# V3.net
KiCad netlist of a schematic drawn in Altium Designer
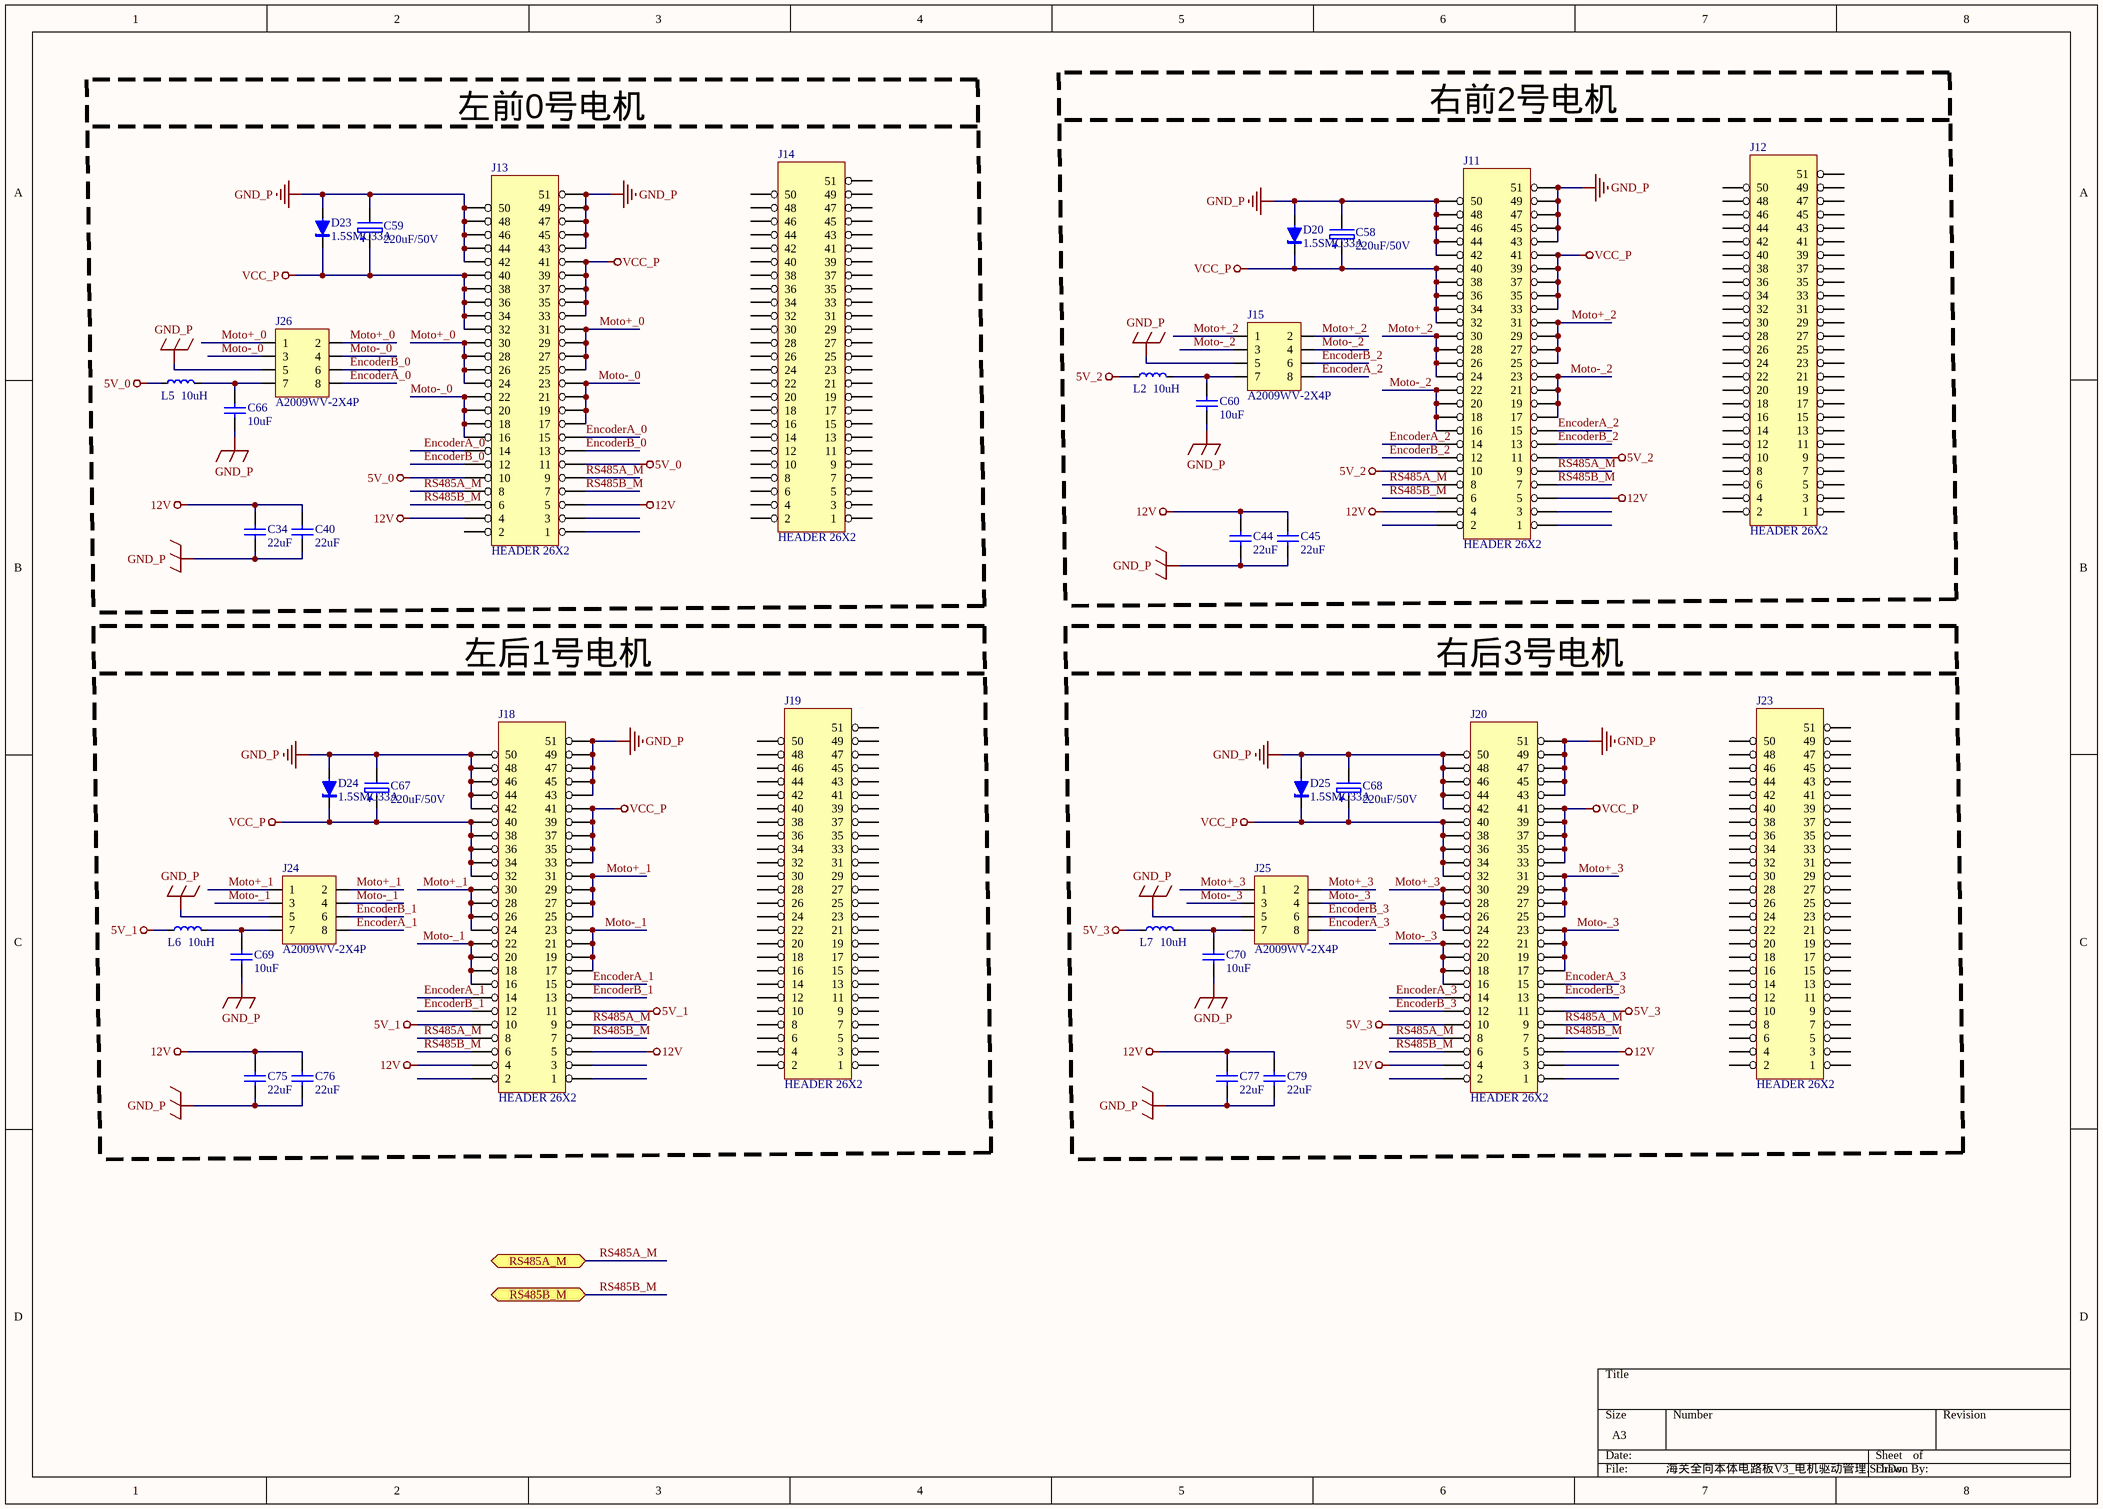
[diagram p0: 海关全向本体电路板V3_电机驱动管理.SchDoc]

(export (version "E")
  (design (tool "Eeschema 10.0.6"))
  (components
    (comp (ref "C34")
      (value "22uF")
      (footprint "C1206-S")
      (description "CAP")
      (fields (field (name "PUBLISHER") "Altium Limited"))
      (libsource (lib "Passive Components Class") (part "CAP"))
    )
    (comp (ref "C40")
      (value "22uF")
      (footprint "C1206-S")
      (description "CAP")
      (fields (field (name "PUBLISHER") "Altium Limited"))
      (libsource (lib "Passive Components Class") (part "CAP"))
    )
    (comp (ref "C44")
      (value "22uF")
      (footprint "C1206-S")
      (description "CAP")
      (fields (field (name "PUBLISHER") "Altium Limited"))
      (libsource (lib "Passive Components Class") (part "CAP"))
    )
    (comp (ref "C45")
      (value "22uF")
      (footprint "C1206-S")
      (description "CAP")
      (fields (field (name "PUBLISHER") "Altium Limited"))
      (libsource (lib "Passive Components Class") (part "CAP"))
    )
    (comp (ref "C58")
      (value "220uF/50V")
      (footprint "CAPPR-10X10-SM")
      (description "Electrolytic Capacitor")
      (libsource (lib "*") (part "ELECTRO"))
    )
    (comp (ref "C59")
      (value "220uF/50V")
      (footprint "CAPPR-10X10-SM")
      (description "Electrolytic Capacitor")
      (libsource (lib "*") (part "ELECTRO"))
    )
    (comp (ref "C60")
      (value "10uF")
      (footprint "C0603-S")
      (description "CAP")
      (fields (field (name "PUBLISHER") "Altium Limited"))
      (libsource (lib "Passive Components Class") (part "CAP"))
    )
    (comp (ref "C66")
      (value "10uF")
      (footprint "C0603-S")
      (description "CAP")
      (fields (field (name "PUBLISHER") "Altium Limited"))
      (libsource (lib "Passive Components Class") (part "CAP"))
    )
    (comp (ref "C67")
      (value "220uF/50V")
      (footprint "CAPPR-10X10-SM")
      (description "Electrolytic Capacitor")
      (libsource (lib "*") (part "ELECTRO"))
    )
    (comp (ref "C68")
      (value "220uF/50V")
      (footprint "CAPPR-10X10-SM")
      (description "Electrolytic Capacitor")
      (libsource (lib "*") (part "ELECTRO"))
    )
    (comp (ref "C69")
      (value "10uF")
      (footprint "C0603-S")
      (description "CAP")
      (fields (field (name "PUBLISHER") "Altium Limited"))
      (libsource (lib "Passive Components Class") (part "CAP"))
    )
    (comp (ref "C70")
      (value "10uF")
      (footprint "C0603-S")
      (description "CAP")
      (fields (field (name "PUBLISHER") "Altium Limited"))
      (libsource (lib "Passive Components Class") (part "CAP"))
    )
    (comp (ref "C75")
      (value "22uF")
      (footprint "C1206-S")
      (description "CAP")
      (fields (field (name "PUBLISHER") "Altium Limited"))
      (libsource (lib "Passive Components Class") (part "CAP"))
    )
    (comp (ref "C76")
      (value "22uF")
      (footprint "C1206-S")
      (description "CAP")
      (fields (field (name "PUBLISHER") "Altium Limited"))
      (libsource (lib "Passive Components Class") (part "CAP"))
    )
    (comp (ref "C77")
      (value "22uF")
      (footprint "C1206-S")
      (description "CAP")
      (fields (field (name "PUBLISHER") "Altium Limited"))
      (libsource (lib "Passive Components Class") (part "CAP"))
    )
    (comp (ref "C79")
      (value "22uF")
      (footprint "C1206-S")
      (description "CAP")
      (fields (field (name "PUBLISHER") "Altium Limited"))
      (libsource (lib "Passive Components Class") (part "CAP"))
    )
    (comp (ref "D20")
      (value "1.5SMC33A")
      (footprint "SMC-S")
      (description "Small Signal Zener Diodes")
      (libsource (lib "Passive Components Class") (part "DIODE-ZENER"))
    )
    (comp (ref "D23")
      (value "1.5SMC33A")
      (footprint "SMC-S")
      (description "Small Signal Zener Diodes")
      (libsource (lib "Passive Components Class") (part "DIODE-ZENER"))
    )
    (comp (ref "D24")
      (value "1.5SMC33A")
      (footprint "SMC-S")
      (description "Small Signal Zener Diodes")
      (libsource (lib "Passive Components Class") (part "DIODE-ZENER"))
    )
    (comp (ref "D25")
      (value "1.5SMC33A")
      (footprint "SMC-S")
      (description "Small Signal Zener Diodes")
      (libsource (lib "Passive Components Class") (part "DIODE-ZENER"))
    )
    (comp (ref "J11")
      (value "HEADER 26X2")
      (footprint "DF9-51P-1V")
      (libsource (lib "Connector Class") (part "HEADER 35X2_1"))
    )
    (comp (ref "J12")
      (value "HEADER 26X2")
      (footprint "DF9-51P-1V")
      (libsource (lib "Connector Class") (part "HEADER 35X2_1"))
    )
    (comp (ref "J13")
      (value "HEADER 26X2")
      (footprint "DF9-51P-1V")
      (libsource (lib "Connector Class") (part "HEADER 35X2_1"))
    )
    (comp (ref "J14")
      (value "HEADER 26X2")
      (footprint "DF9-51P-1V")
      (libsource (lib "Connector Class") (part "HEADER 35X2_1"))
    )
    (comp (ref "J15")
      (value "A2009WV-2X4P")
      (footprint "A2009WV-2X4P")
      (libsource (lib "Connector Class") (part "A2009WV-2X5P"))
    )
    (comp (ref "J18")
      (value "HEADER 26X2")
      (footprint "DF9-51P-1V")
      (libsource (lib "Connector Class") (part "HEADER 35X2_1"))
    )
    (comp (ref "J19")
      (value "HEADER 26X2")
      (footprint "DF9-51P-1V")
      (libsource (lib "Connector Class") (part "HEADER 35X2_1"))
    )
    (comp (ref "J20")
      (value "HEADER 26X2")
      (footprint "DF9-51P-1V")
      (libsource (lib "Connector Class") (part "HEADER 35X2_1"))
    )
    (comp (ref "J23")
      (value "HEADER 26X2")
      (footprint "DF9-51P-1V")
      (libsource (lib "Connector Class") (part "HEADER 35X2_1"))
    )
    (comp (ref "J24")
      (value "A2009WV-2X4P")
      (footprint "A2009WV-2X4P")
      (libsource (lib "Connector Class") (part "A2009WV-2X5P"))
    )
    (comp (ref "J25")
      (value "A2009WV-2X4P")
      (footprint "A2009WV-2X4P")
      (libsource (lib "Connector Class") (part "A2009WV-2X5P"))
    )
    (comp (ref "J26")
      (value "A2009WV-2X4P")
      (footprint "A2009WV-2X4P")
      (libsource (lib "Connector Class") (part "HEADER2X4"))
    )
    (comp (ref "L2")
      (value "10uH")
      (footprint "L0805-C")
      (description "INDUCTOR")
      (fields (field (name "PUBLISHER") "Altium Limited"))
      (libsource (lib "Passive Components Class") (part "INDUCTOR"))
    )
    (comp (ref "L5")
      (value "10uH")
      (footprint "L0805-C")
      (description "INDUCTOR")
      (fields (field (name "PUBLISHER") "Altium Limited"))
      (libsource (lib "Passive Components Class") (part "INDUCTOR"))
    )
    (comp (ref "L6")
      (value "10uH")
      (footprint "L0805-C")
      (description "INDUCTOR")
      (fields (field (name "PUBLISHER") "Altium Limited"))
      (libsource (lib "Passive Components Class") (part "INDUCTOR"))
    )
    (comp (ref "L7")
      (value "10uH")
      (footprint "L0805-C")
      (description "INDUCTOR")
      (fields (field (name "PUBLISHER") "Altium Limited"))
      (libsource (lib "Passive Components Class") (part "INDUCTOR"))
    )
  )
  (nets
    (net (code "1") (name "/EncoderA_0") (class "Default")
      (node (ref "J13") (pin "14") (pinfunction "14_14") (pintype "passive"))
      (node (ref "J13") (pin "15") (pinfunction "15_15") (pintype "passive"))
      (node (ref "J26") (pin "8") (pinfunction "8_8") (pintype "passive"))
    )
    (net (code "2") (name "/EncoderA_1") (class "Default")
      (node (ref "J18") (pin "14") (pinfunction "14_14") (pintype "passive"))
      (node (ref "J18") (pin "15") (pinfunction "15_15") (pintype "passive"))
      (node (ref "J24") (pin "8") (pinfunction "8_8") (pintype "passive"))
    )
    (net (code "3") (name "/EncoderA_2") (class "Default")
      (node (ref "J11") (pin "14") (pinfunction "14_14") (pintype "passive"))
      (node (ref "J11") (pin "15") (pinfunction "15_15") (pintype "passive"))
      (node (ref "J15") (pin "8") (pinfunction "8_8") (pintype "passive"))
    )
    (net (code "4") (name "/EncoderA_3") (class "Default")
      (node (ref "J20") (pin "14") (pinfunction "14_14") (pintype "passive"))
      (node (ref "J20") (pin "15") (pinfunction "15_15") (pintype "passive"))
      (node (ref "J25") (pin "8") (pinfunction "8_8") (pintype "passive"))
    )
    (net (code "5") (name "/EncoderB_0") (class "Default")
      (node (ref "J13") (pin "12") (pinfunction "12_12") (pintype "passive"))
      (node (ref "J13") (pin "13") (pinfunction "13_13") (pintype "passive"))
      (node (ref "J26") (pin "6") (pinfunction "6_6") (pintype "passive"))
    )
    (net (code "6") (name "/EncoderB_1") (class "Default")
      (node (ref "J18") (pin "12") (pinfunction "12_12") (pintype "passive"))
      (node (ref "J18") (pin "13") (pinfunction "13_13") (pintype "passive"))
      (node (ref "J24") (pin "6") (pinfunction "6_6") (pintype "passive"))
    )
    (net (code "7") (name "/EncoderB_2") (class "Default")
      (node (ref "J11") (pin "12") (pinfunction "12_12") (pintype "passive"))
      (node (ref "J11") (pin "13") (pinfunction "13_13") (pintype "passive"))
      (node (ref "J15") (pin "6") (pinfunction "6_6") (pintype "passive"))
    )
    (net (code "8") (name "/EncoderB_3") (class "Default")
      (node (ref "J20") (pin "12") (pinfunction "12_12") (pintype "passive"))
      (node (ref "J20") (pin "13") (pinfunction "13_13") (pintype "passive"))
      (node (ref "J25") (pin "6") (pinfunction "6_6") (pintype "passive"))
    )
    (net (code "9") (name "/Moto+_0") (class "Default")
      (node (ref "J13") (pin "24") (pinfunction "24_24") (pintype "passive"))
      (node (ref "J13") (pin "25") (pinfunction "25_25") (pintype "passive"))
      (node (ref "J13") (pin "26") (pinfunction "26_26") (pintype "passive"))
      (node (ref "J13") (pin "27") (pinfunction "27_27") (pintype "passive"))
      (node (ref "J13") (pin "28") (pinfunction "28_28") (pintype "passive"))
      (node (ref "J13") (pin "29") (pinfunction "29_29") (pintype "passive"))
      (node (ref "J13") (pin "30") (pinfunction "30_30") (pintype "passive"))
      (node (ref "J13") (pin "31") (pinfunction "31_31") (pintype "passive"))
      (node (ref "J26") (pin "1") (pinfunction "1_1") (pintype "passive"))
      (node (ref "J26") (pin "2") (pinfunction "2_2") (pintype "passive"))
    )
    (net (code "10") (name "/Moto+_1") (class "Default")
      (node (ref "J18") (pin "24") (pinfunction "24_24") (pintype "passive"))
      (node (ref "J18") (pin "25") (pinfunction "25_25") (pintype "passive"))
      (node (ref "J18") (pin "26") (pinfunction "26_26") (pintype "passive"))
      (node (ref "J18") (pin "27") (pinfunction "27_27") (pintype "passive"))
      (node (ref "J18") (pin "28") (pinfunction "28_28") (pintype "passive"))
      (node (ref "J18") (pin "29") (pinfunction "29_29") (pintype "passive"))
      (node (ref "J18") (pin "30") (pinfunction "30_30") (pintype "passive"))
      (node (ref "J18") (pin "31") (pinfunction "31_31") (pintype "passive"))
      (node (ref "J24") (pin "1") (pinfunction "1_1") (pintype "passive"))
      (node (ref "J24") (pin "2") (pinfunction "2_2") (pintype "passive"))
    )
    (net (code "11") (name "/Moto+_2") (class "Default")
      (node (ref "J11") (pin "24") (pinfunction "24_24") (pintype "passive"))
      (node (ref "J11") (pin "25") (pinfunction "25_25") (pintype "passive"))
      (node (ref "J11") (pin "26") (pinfunction "26_26") (pintype "passive"))
      (node (ref "J11") (pin "27") (pinfunction "27_27") (pintype "passive"))
      (node (ref "J11") (pin "28") (pinfunction "28_28") (pintype "passive"))
      (node (ref "J11") (pin "29") (pinfunction "29_29") (pintype "passive"))
      (node (ref "J11") (pin "30") (pinfunction "30_30") (pintype "passive"))
      (node (ref "J11") (pin "31") (pinfunction "31_31") (pintype "passive"))
      (node (ref "J15") (pin "1") (pinfunction "1_1") (pintype "passive"))
      (node (ref "J15") (pin "2") (pinfunction "2_2") (pintype "passive"))
    )
    (net (code "12") (name "/Moto+_3") (class "Default")
      (node (ref "J20") (pin "24") (pinfunction "24_24") (pintype "passive"))
      (node (ref "J20") (pin "25") (pinfunction "25_25") (pintype "passive"))
      (node (ref "J20") (pin "26") (pinfunction "26_26") (pintype "passive"))
      (node (ref "J20") (pin "27") (pinfunction "27_27") (pintype "passive"))
      (node (ref "J20") (pin "28") (pinfunction "28_28") (pintype "passive"))
      (node (ref "J20") (pin "29") (pinfunction "29_29") (pintype "passive"))
      (node (ref "J20") (pin "30") (pinfunction "30_30") (pintype "passive"))
      (node (ref "J20") (pin "31") (pinfunction "31_31") (pintype "passive"))
      (node (ref "J25") (pin "1") (pinfunction "1_1") (pintype "passive"))
      (node (ref "J25") (pin "2") (pinfunction "2_2") (pintype "passive"))
    )
    (net (code "13") (name "/Moto-_0") (class "Default")
      (node (ref "J13") (pin "16") (pinfunction "16_16") (pintype "passive"))
      (node (ref "J13") (pin "17") (pinfunction "17_17") (pintype "passive"))
      (node (ref "J13") (pin "18") (pinfunction "18_18") (pintype "passive"))
      (node (ref "J13") (pin "19") (pinfunction "19_19") (pintype "passive"))
      (node (ref "J13") (pin "20") (pinfunction "20_20") (pintype "passive"))
      (node (ref "J13") (pin "21") (pinfunction "21_21") (pintype "passive"))
      (node (ref "J13") (pin "22") (pinfunction "22_22") (pintype "passive"))
      (node (ref "J13") (pin "23") (pinfunction "23_23") (pintype "passive"))
      (node (ref "J26") (pin "3") (pinfunction "3_3") (pintype "passive"))
      (node (ref "J26") (pin "4") (pinfunction "4_4") (pintype "passive"))
    )
    (net (code "14") (name "/Moto-_1") (class "Default")
      (node (ref "J18") (pin "16") (pinfunction "16_16") (pintype "passive"))
      (node (ref "J18") (pin "17") (pinfunction "17_17") (pintype "passive"))
      (node (ref "J18") (pin "18") (pinfunction "18_18") (pintype "passive"))
      (node (ref "J18") (pin "19") (pinfunction "19_19") (pintype "passive"))
      (node (ref "J18") (pin "20") (pinfunction "20_20") (pintype "passive"))
      (node (ref "J18") (pin "21") (pinfunction "21_21") (pintype "passive"))
      (node (ref "J18") (pin "22") (pinfunction "22_22") (pintype "passive"))
      (node (ref "J18") (pin "23") (pinfunction "23_23") (pintype "passive"))
      (node (ref "J24") (pin "3") (pinfunction "3_3") (pintype "passive"))
      (node (ref "J24") (pin "4") (pinfunction "4_4") (pintype "passive"))
    )
    (net (code "15") (name "/Moto-_2") (class "Default")
      (node (ref "J11") (pin "16") (pinfunction "16_16") (pintype "passive"))
      (node (ref "J11") (pin "17") (pinfunction "17_17") (pintype "passive"))
      (node (ref "J11") (pin "18") (pinfunction "18_18") (pintype "passive"))
      (node (ref "J11") (pin "19") (pinfunction "19_19") (pintype "passive"))
      (node (ref "J11") (pin "20") (pinfunction "20_20") (pintype "passive"))
      (node (ref "J11") (pin "21") (pinfunction "21_21") (pintype "passive"))
      (node (ref "J11") (pin "22") (pinfunction "22_22") (pintype "passive"))
      (node (ref "J11") (pin "23") (pinfunction "23_23") (pintype "passive"))
      (node (ref "J15") (pin "3") (pinfunction "3_3") (pintype "passive"))
      (node (ref "J15") (pin "4") (pinfunction "4_4") (pintype "passive"))
    )
    (net (code "16") (name "/Moto-_3") (class "Default")
      (node (ref "J20") (pin "16") (pinfunction "16_16") (pintype "passive"))
      (node (ref "J20") (pin "17") (pinfunction "17_17") (pintype "passive"))
      (node (ref "J20") (pin "18") (pinfunction "18_18") (pintype "passive"))
      (node (ref "J20") (pin "19") (pinfunction "19_19") (pintype "passive"))
      (node (ref "J20") (pin "20") (pinfunction "20_20") (pintype "passive"))
      (node (ref "J20") (pin "21") (pinfunction "21_21") (pintype "passive"))
      (node (ref "J20") (pin "22") (pinfunction "22_22") (pintype "passive"))
      (node (ref "J20") (pin "23") (pinfunction "23_23") (pintype "passive"))
      (node (ref "J25") (pin "3") (pinfunction "3_3") (pintype "passive"))
      (node (ref "J25") (pin "4") (pinfunction "4_4") (pintype "passive"))
    )
    (net (code "17") (name "/RS485A_M") (class "Default")
      (node (ref "J11") (pin "8") (pinfunction "8_8") (pintype "passive"))
      (node (ref "J11") (pin "9") (pinfunction "9_9") (pintype "passive"))
      (node (ref "J13") (pin "8") (pinfunction "8_8") (pintype "passive"))
      (node (ref "J13") (pin "9") (pinfunction "9_9") (pintype "passive"))
      (node (ref "J18") (pin "8") (pinfunction "8_8") (pintype "passive"))
      (node (ref "J18") (pin "9") (pinfunction "9_9") (pintype "passive"))
      (node (ref "J20") (pin "8") (pinfunction "8_8") (pintype "passive"))
      (node (ref "J20") (pin "9") (pinfunction "9_9") (pintype "passive"))
    )
    (net (code "18") (name "/RS485B_M") (class "Default")
      (node (ref "J11") (pin "6") (pinfunction "6_6") (pintype "passive"))
      (node (ref "J11") (pin "7") (pinfunction "7_7") (pintype "passive"))
      (node (ref "J13") (pin "6") (pinfunction "6_6") (pintype "passive"))
      (node (ref "J13") (pin "7") (pinfunction "7_7") (pintype "passive"))
      (node (ref "J18") (pin "6") (pinfunction "6_6") (pintype "passive"))
      (node (ref "J18") (pin "7") (pinfunction "7_7") (pintype "passive"))
      (node (ref "J20") (pin "6") (pinfunction "6_6") (pintype "passive"))
      (node (ref "J20") (pin "7") (pinfunction "7_7") (pintype "passive"))
    )
    (net (code "19") (name "5V_0") (class "Default")
      (node (ref "J13") (pin "10") (pinfunction "10_10") (pintype "passive"))
      (node (ref "J13") (pin "11") (pinfunction "11_11") (pintype "passive"))
      (node (ref "L5") (pin "1") (pinfunction "1_1") (pintype "passive"))
    )
    (net (code "20") (name "5V_1") (class "Default")
      (node (ref "J18") (pin "10") (pinfunction "10_10") (pintype "passive"))
      (node (ref "J18") (pin "11") (pinfunction "11_11") (pintype "passive"))
      (node (ref "L6") (pin "1") (pinfunction "1_1") (pintype "passive"))
    )
    (net (code "21") (name "5V_2") (class "Default")
      (node (ref "J11") (pin "10") (pinfunction "10_10") (pintype "passive"))
      (node (ref "J11") (pin "11") (pinfunction "11_11") (pintype "passive"))
      (node (ref "L2") (pin "1") (pinfunction "1_1") (pintype "passive"))
    )
    (net (code "22") (name "5V_3") (class "Default")
      (node (ref "J20") (pin "10") (pinfunction "10_10") (pintype "passive"))
      (node (ref "J20") (pin "11") (pinfunction "11_11") (pintype "passive"))
      (node (ref "L7") (pin "1") (pinfunction "1_1") (pintype "passive"))
    )
    (net (code "23") (name "12V") (class "Default")
      (node (ref "C34") (pin "1") (pinfunction "1_1") (pintype "passive"))
      (node (ref "C40") (pin "1") (pinfunction "1_1") (pintype "passive"))
      (node (ref "C44") (pin "1") (pinfunction "1_1") (pintype "passive"))
      (node (ref "C45") (pin "1") (pinfunction "1_1") (pintype "passive"))
      (node (ref "C75") (pin "1") (pinfunction "1_1") (pintype "passive"))
      (node (ref "C76") (pin "1") (pinfunction "1_1") (pintype "passive"))
      (node (ref "C77") (pin "1") (pinfunction "1_1") (pintype "passive"))
      (node (ref "C79") (pin "1") (pinfunction "1_1") (pintype "passive"))
      (node (ref "J11") (pin "4") (pinfunction "4_4") (pintype "passive"))
      (node (ref "J11") (pin "5") (pinfunction "5_5") (pintype "passive"))
      (node (ref "J13") (pin "4") (pinfunction "4_4") (pintype "passive"))
      (node (ref "J13") (pin "5") (pinfunction "5_5") (pintype "passive"))
      (node (ref "J18") (pin "4") (pinfunction "4_4") (pintype "passive"))
      (node (ref "J18") (pin "5") (pinfunction "5_5") (pintype "passive"))
      (node (ref "J20") (pin "4") (pinfunction "4_4") (pintype "passive"))
      (node (ref "J20") (pin "5") (pinfunction "5_5") (pintype "passive"))
    )
    (net (code "24") (name "GND_P") (class "Default")
      (node (ref "C34") (pin "2") (pinfunction "2_2") (pintype "passive"))
      (node (ref "C40") (pin "2") (pinfunction "2_2") (pintype "passive"))
      (node (ref "C44") (pin "2") (pinfunction "2_2") (pintype "passive"))
      (node (ref "C45") (pin "2") (pinfunction "2_2") (pintype "passive"))
      (node (ref "C58") (pin "2") (pinfunction "2_2") (pintype "passive"))
      (node (ref "C59") (pin "2") (pinfunction "2_2") (pintype "passive"))
      (node (ref "C60") (pin "2") (pinfunction "2_2") (pintype "passive"))
      (node (ref "C66") (pin "2") (pinfunction "2_2") (pintype "passive"))
      (node (ref "C67") (pin "2") (pinfunction "2_2") (pintype "passive"))
      (node (ref "C68") (pin "2") (pinfunction "2_2") (pintype "passive"))
      (node (ref "C69") (pin "2") (pinfunction "2_2") (pintype "passive"))
      (node (ref "C70") (pin "2") (pinfunction "2_2") (pintype "passive"))
      (node (ref "C75") (pin "2") (pinfunction "2_2") (pintype "passive"))
      (node (ref "C76") (pin "2") (pinfunction "2_2") (pintype "passive"))
      (node (ref "C77") (pin "2") (pinfunction "2_2") (pintype "passive"))
      (node (ref "C79") (pin "2") (pinfunction "2_2") (pintype "passive"))
      (node (ref "D20") (pin "1") (pinfunction "A_1") (pintype "passive"))
      (node (ref "D23") (pin "1") (pinfunction "A_1") (pintype "passive"))
      (node (ref "D24") (pin "1") (pinfunction "A_1") (pintype "passive"))
      (node (ref "D25") (pin "1") (pinfunction "A_1") (pintype "passive"))
      (node (ref "J11") (pin "42") (pinfunction "42_42") (pintype "passive"))
      (node (ref "J11") (pin "43") (pinfunction "43_43") (pintype "passive"))
      (node (ref "J11") (pin "44") (pinfunction "44_44") (pintype "passive"))
      (node (ref "J11") (pin "45") (pinfunction "45_45") (pintype "passive"))
      (node (ref "J11") (pin "46") (pinfunction "46_46") (pintype "passive"))
      (node (ref "J11") (pin "47") (pinfunction "47_47") (pintype "passive"))
      (node (ref "J11") (pin "48") (pinfunction "48_48") (pintype "passive"))
      (node (ref "J11") (pin "49") (pinfunction "49_49") (pintype "passive"))
      (node (ref "J11") (pin "50") (pinfunction "50_50") (pintype "passive"))
      (node (ref "J11") (pin "51") (pinfunction "51_51") (pintype "passive"))
      (node (ref "J13") (pin "42") (pinfunction "42_42") (pintype "passive"))
      (node (ref "J13") (pin "43") (pinfunction "43_43") (pintype "passive"))
      (node (ref "J13") (pin "44") (pinfunction "44_44") (pintype "passive"))
      (node (ref "J13") (pin "45") (pinfunction "45_45") (pintype "passive"))
      (node (ref "J13") (pin "46") (pinfunction "46_46") (pintype "passive"))
      (node (ref "J13") (pin "47") (pinfunction "47_47") (pintype "passive"))
      (node (ref "J13") (pin "48") (pinfunction "48_48") (pintype "passive"))
      (node (ref "J13") (pin "49") (pinfunction "49_49") (pintype "passive"))
      (node (ref "J13") (pin "50") (pinfunction "50_50") (pintype "passive"))
      (node (ref "J13") (pin "51") (pinfunction "51_51") (pintype "passive"))
      (node (ref "J15") (pin "5") (pinfunction "5_5") (pintype "passive"))
      (node (ref "J18") (pin "42") (pinfunction "42_42") (pintype "passive"))
      (node (ref "J18") (pin "43") (pinfunction "43_43") (pintype "passive"))
      (node (ref "J18") (pin "44") (pinfunction "44_44") (pintype "passive"))
      (node (ref "J18") (pin "45") (pinfunction "45_45") (pintype "passive"))
      (node (ref "J18") (pin "46") (pinfunction "46_46") (pintype "passive"))
      (node (ref "J18") (pin "47") (pinfunction "47_47") (pintype "passive"))
      (node (ref "J18") (pin "48") (pinfunction "48_48") (pintype "passive"))
      (node (ref "J18") (pin "49") (pinfunction "49_49") (pintype "passive"))
      (node (ref "J18") (pin "50") (pinfunction "50_50") (pintype "passive"))
      (node (ref "J18") (pin "51") (pinfunction "51_51") (pintype "passive"))
      (node (ref "J20") (pin "42") (pinfunction "42_42") (pintype "passive"))
      (node (ref "J20") (pin "43") (pinfunction "43_43") (pintype "passive"))
      (node (ref "J20") (pin "44") (pinfunction "44_44") (pintype "passive"))
      (node (ref "J20") (pin "45") (pinfunction "45_45") (pintype "passive"))
      (node (ref "J20") (pin "46") (pinfunction "46_46") (pintype "passive"))
      (node (ref "J20") (pin "47") (pinfunction "47_47") (pintype "passive"))
      (node (ref "J20") (pin "48") (pinfunction "48_48") (pintype "passive"))
      (node (ref "J20") (pin "49") (pinfunction "49_49") (pintype "passive"))
      (node (ref "J20") (pin "50") (pinfunction "50_50") (pintype "passive"))
      (node (ref "J20") (pin "51") (pinfunction "51_51") (pintype "passive"))
      (node (ref "J24") (pin "5") (pinfunction "5_5") (pintype "passive"))
      (node (ref "J25") (pin "5") (pinfunction "5_5") (pintype "passive"))
      (node (ref "J26") (pin "5") (pinfunction "5_5") (pintype "passive"))
    )
    (net (code "25") (name "Net-(C60-Pad1)") (class "Default")
      (node (ref "C60") (pin "1") (pinfunction "1_1") (pintype "passive"))
      (node (ref "J15") (pin "7") (pinfunction "7_7") (pintype "passive"))
      (node (ref "L2") (pin "2") (pinfunction "2_2") (pintype "passive"))
    )
    (net (code "26") (name "Net-(C66-Pad1)") (class "Default")
      (node (ref "C66") (pin "1") (pinfunction "1_1") (pintype "passive"))
      (node (ref "J26") (pin "7") (pinfunction "7_7") (pintype "passive"))
      (node (ref "L5") (pin "2") (pinfunction "2_2") (pintype "passive"))
    )
    (net (code "27") (name "Net-(C69-Pad1)") (class "Default")
      (node (ref "C69") (pin "1") (pinfunction "1_1") (pintype "passive"))
      (node (ref "J24") (pin "7") (pinfunction "7_7") (pintype "passive"))
      (node (ref "L6") (pin "2") (pinfunction "2_2") (pintype "passive"))
    )
    (net (code "28") (name "Net-(C70-Pad1)") (class "Default")
      (node (ref "C70") (pin "1") (pinfunction "1_1") (pintype "passive"))
      (node (ref "J25") (pin "7") (pinfunction "7_7") (pintype "passive"))
      (node (ref "L7") (pin "2") (pinfunction "2_2") (pintype "passive"))
    )
    (net (code "29") (name "VCC_P") (class "Default")
      (node (ref "C58") (pin "1") (pinfunction "1_1") (pintype "passive"))
      (node (ref "C59") (pin "1") (pinfunction "1_1") (pintype "passive"))
      (node (ref "C67") (pin "1") (pinfunction "1_1") (pintype "passive"))
      (node (ref "C68") (pin "1") (pinfunction "1_1") (pintype "passive"))
      (node (ref "D20") (pin "2") (pinfunction "K_2") (pintype "passive"))
      (node (ref "D23") (pin "2") (pinfunction "K_2") (pintype "passive"))
      (node (ref "D24") (pin "2") (pinfunction "K_2") (pintype "passive"))
      (node (ref "D25") (pin "2") (pinfunction "K_2") (pintype "passive"))
      (node (ref "J11") (pin "32") (pinfunction "32_32") (pintype "passive"))
      (node (ref "J11") (pin "33") (pinfunction "33_33") (pintype "passive"))
      (node (ref "J11") (pin "34") (pinfunction "34_34") (pintype "passive"))
      (node (ref "J11") (pin "35") (pinfunction "35_35") (pintype "passive"))
      (node (ref "J11") (pin "36") (pinfunction "36_36") (pintype "passive"))
      (node (ref "J11") (pin "37") (pinfunction "37_37") (pintype "passive"))
      (node (ref "J11") (pin "38") (pinfunction "38_38") (pintype "passive"))
      (node (ref "J11") (pin "39") (pinfunction "39_39") (pintype "passive"))
      (node (ref "J11") (pin "40") (pinfunction "40_40") (pintype "passive"))
      (node (ref "J11") (pin "41") (pinfunction "41_41") (pintype "passive"))
      (node (ref "J13") (pin "32") (pinfunction "32_32") (pintype "passive"))
      (node (ref "J13") (pin "33") (pinfunction "33_33") (pintype "passive"))
      (node (ref "J13") (pin "34") (pinfunction "34_34") (pintype "passive"))
      (node (ref "J13") (pin "35") (pinfunction "35_35") (pintype "passive"))
      (node (ref "J13") (pin "36") (pinfunction "36_36") (pintype "passive"))
      (node (ref "J13") (pin "37") (pinfunction "37_37") (pintype "passive"))
      (node (ref "J13") (pin "38") (pinfunction "38_38") (pintype "passive"))
      (node (ref "J13") (pin "39") (pinfunction "39_39") (pintype "passive"))
      (node (ref "J13") (pin "40") (pinfunction "40_40") (pintype "passive"))
      (node (ref "J13") (pin "41") (pinfunction "41_41") (pintype "passive"))
      (node (ref "J18") (pin "32") (pinfunction "32_32") (pintype "passive"))
      (node (ref "J18") (pin "33") (pinfunction "33_33") (pintype "passive"))
      (node (ref "J18") (pin "34") (pinfunction "34_34") (pintype "passive"))
      (node (ref "J18") (pin "35") (pinfunction "35_35") (pintype "passive"))
      (node (ref "J18") (pin "36") (pinfunction "36_36") (pintype "passive"))
      (node (ref "J18") (pin "37") (pinfunction "37_37") (pintype "passive"))
      (node (ref "J18") (pin "38") (pinfunction "38_38") (pintype "passive"))
      (node (ref "J18") (pin "39") (pinfunction "39_39") (pintype "passive"))
      (node (ref "J18") (pin "40") (pinfunction "40_40") (pintype "passive"))
      (node (ref "J18") (pin "41") (pinfunction "41_41") (pintype "passive"))
      (node (ref "J20") (pin "32") (pinfunction "32_32") (pintype "passive"))
      (node (ref "J20") (pin "33") (pinfunction "33_33") (pintype "passive"))
      (node (ref "J20") (pin "34") (pinfunction "34_34") (pintype "passive"))
      (node (ref "J20") (pin "35") (pinfunction "35_35") (pintype "passive"))
      (node (ref "J20") (pin "36") (pinfunction "36_36") (pintype "passive"))
      (node (ref "J20") (pin "37") (pinfunction "37_37") (pintype "passive"))
      (node (ref "J20") (pin "38") (pinfunction "38_38") (pintype "passive"))
      (node (ref "J20") (pin "39") (pinfunction "39_39") (pintype "passive"))
      (node (ref "J20") (pin "40") (pinfunction "40_40") (pintype "passive"))
      (node (ref "J20") (pin "41") (pinfunction "41_41") (pintype "passive"))
    )
    (net (code "30") (name "unconnected-(J11-Pad1)") (class "Default")
      (node (ref "J11") (pin "1") (pinfunction "1_1") (pintype "passive"))
    )
    (net (code "31") (name "unconnected-(J11-Pad2)") (class "Default")
      (node (ref "J11") (pin "2") (pinfunction "2_2") (pintype "passive"))
    )
    (net (code "32") (name "unconnected-(J11-Pad3)") (class "Default")
      (node (ref "J11") (pin "3") (pinfunction "3_3") (pintype "passive"))
    )
    (net (code "33") (name "unconnected-(J12-Pad1)") (class "Default")
      (node (ref "J12") (pin "1") (pinfunction "1_1") (pintype "passive"))
    )
    (net (code "34") (name "unconnected-(J12-Pad2)") (class "Default")
      (node (ref "J12") (pin "2") (pinfunction "2_2") (pintype "passive"))
    )
    (net (code "35") (name "unconnected-(J12-Pad3)") (class "Default")
      (node (ref "J12") (pin "3") (pinfunction "3_3") (pintype "passive"))
    )
    (net (code "36") (name "unconnected-(J12-Pad4)") (class "Default")
      (node (ref "J12") (pin "4") (pinfunction "4_4") (pintype "passive"))
    )
    (net (code "37") (name "unconnected-(J12-Pad5)") (class "Default")
      (node (ref "J12") (pin "5") (pinfunction "5_5") (pintype "passive"))
    )
    (net (code "38") (name "unconnected-(J12-Pad6)") (class "Default")
      (node (ref "J12") (pin "6") (pinfunction "6_6") (pintype "passive"))
    )
    (net (code "39") (name "unconnected-(J12-Pad7)") (class "Default")
      (node (ref "J12") (pin "7") (pinfunction "7_7") (pintype "passive"))
    )
    (net (code "40") (name "unconnected-(J12-Pad8)") (class "Default")
      (node (ref "J12") (pin "8") (pinfunction "8_8") (pintype "passive"))
    )
    (net (code "41") (name "unconnected-(J12-Pad9)") (class "Default")
      (node (ref "J12") (pin "9") (pinfunction "9_9") (pintype "passive"))
    )
    (net (code "42") (name "unconnected-(J12-Pad10)") (class "Default")
      (node (ref "J12") (pin "10") (pinfunction "10_10") (pintype "passive"))
    )
    (net (code "43") (name "unconnected-(J12-Pad11)") (class "Default")
      (node (ref "J12") (pin "11") (pinfunction "11_11") (pintype "passive"))
    )
    (net (code "44") (name "unconnected-(J12-Pad12)") (class "Default")
      (node (ref "J12") (pin "12") (pinfunction "12_12") (pintype "passive"))
    )
    (net (code "45") (name "unconnected-(J12-Pad13)") (class "Default")
      (node (ref "J12") (pin "13") (pinfunction "13_13") (pintype "passive"))
    )
    (net (code "46") (name "unconnected-(J12-Pad14)") (class "Default")
      (node (ref "J12") (pin "14") (pinfunction "14_14") (pintype "passive"))
    )
    (net (code "47") (name "unconnected-(J12-Pad15)") (class "Default")
      (node (ref "J12") (pin "15") (pinfunction "15_15") (pintype "passive"))
    )
    (net (code "48") (name "unconnected-(J12-Pad16)") (class "Default")
      (node (ref "J12") (pin "16") (pinfunction "16_16") (pintype "passive"))
    )
    (net (code "49") (name "unconnected-(J12-Pad17)") (class "Default")
      (node (ref "J12") (pin "17") (pinfunction "17_17") (pintype "passive"))
    )
    (net (code "50") (name "unconnected-(J12-Pad18)") (class "Default")
      (node (ref "J12") (pin "18") (pinfunction "18_18") (pintype "passive"))
    )
    (net (code "51") (name "unconnected-(J12-Pad19)") (class "Default")
      (node (ref "J12") (pin "19") (pinfunction "19_19") (pintype "passive"))
    )
    (net (code "52") (name "unconnected-(J12-Pad20)") (class "Default")
      (node (ref "J12") (pin "20") (pinfunction "20_20") (pintype "passive"))
    )
    (net (code "53") (name "unconnected-(J12-Pad21)") (class "Default")
      (node (ref "J12") (pin "21") (pinfunction "21_21") (pintype "passive"))
    )
    (net (code "54") (name "unconnected-(J12-Pad22)") (class "Default")
      (node (ref "J12") (pin "22") (pinfunction "22_22") (pintype "passive"))
    )
    (net (code "55") (name "unconnected-(J12-Pad23)") (class "Default")
      (node (ref "J12") (pin "23") (pinfunction "23_23") (pintype "passive"))
    )
    (net (code "56") (name "unconnected-(J12-Pad24)") (class "Default")
      (node (ref "J12") (pin "24") (pinfunction "24_24") (pintype "passive"))
    )
    (net (code "57") (name "unconnected-(J12-Pad25)") (class "Default")
      (node (ref "J12") (pin "25") (pinfunction "25_25") (pintype "passive"))
    )
    (net (code "58") (name "unconnected-(J12-Pad26)") (class "Default")
      (node (ref "J12") (pin "26") (pinfunction "26_26") (pintype "passive"))
    )
    (net (code "59") (name "unconnected-(J12-Pad27)") (class "Default")
      (node (ref "J12") (pin "27") (pinfunction "27_27") (pintype "passive"))
    )
    (net (code "60") (name "unconnected-(J12-Pad28)") (class "Default")
      (node (ref "J12") (pin "28") (pinfunction "28_28") (pintype "passive"))
    )
    (net (code "61") (name "unconnected-(J12-Pad29)") (class "Default")
      (node (ref "J12") (pin "29") (pinfunction "29_29") (pintype "passive"))
    )
    (net (code "62") (name "unconnected-(J12-Pad30)") (class "Default")
      (node (ref "J12") (pin "30") (pinfunction "30_30") (pintype "passive"))
    )
    (net (code "63") (name "unconnected-(J12-Pad31)") (class "Default")
      (node (ref "J12") (pin "31") (pinfunction "31_31") (pintype "passive"))
    )
    (net (code "64") (name "unconnected-(J12-Pad32)") (class "Default")
      (node (ref "J12") (pin "32") (pinfunction "32_32") (pintype "passive"))
    )
    (net (code "65") (name "unconnected-(J12-Pad33)") (class "Default")
      (node (ref "J12") (pin "33") (pinfunction "33_33") (pintype "passive"))
    )
    (net (code "66") (name "unconnected-(J12-Pad34)") (class "Default")
      (node (ref "J12") (pin "34") (pinfunction "34_34") (pintype "passive"))
    )
    (net (code "67") (name "unconnected-(J12-Pad35)") (class "Default")
      (node (ref "J12") (pin "35") (pinfunction "35_35") (pintype "passive"))
    )
    (net (code "68") (name "unconnected-(J12-Pad36)") (class "Default")
      (node (ref "J12") (pin "36") (pinfunction "36_36") (pintype "passive"))
    )
    (net (code "69") (name "unconnected-(J12-Pad37)") (class "Default")
      (node (ref "J12") (pin "37") (pinfunction "37_37") (pintype "passive"))
    )
    (net (code "70") (name "unconnected-(J12-Pad38)") (class "Default")
      (node (ref "J12") (pin "38") (pinfunction "38_38") (pintype "passive"))
    )
    (net (code "71") (name "unconnected-(J12-Pad39)") (class "Default")
      (node (ref "J12") (pin "39") (pinfunction "39_39") (pintype "passive"))
    )
    (net (code "72") (name "unconnected-(J12-Pad40)") (class "Default")
      (node (ref "J12") (pin "40") (pinfunction "40_40") (pintype "passive"))
    )
    (net (code "73") (name "unconnected-(J12-Pad41)") (class "Default")
      (node (ref "J12") (pin "41") (pinfunction "41_41") (pintype "passive"))
    )
    (net (code "74") (name "unconnected-(J12-Pad42)") (class "Default")
      (node (ref "J12") (pin "42") (pinfunction "42_42") (pintype "passive"))
    )
    (net (code "75") (name "unconnected-(J12-Pad43)") (class "Default")
      (node (ref "J12") (pin "43") (pinfunction "43_43") (pintype "passive"))
    )
    (net (code "76") (name "unconnected-(J12-Pad44)") (class "Default")
      (node (ref "J12") (pin "44") (pinfunction "44_44") (pintype "passive"))
    )
    (net (code "77") (name "unconnected-(J12-Pad45)") (class "Default")
      (node (ref "J12") (pin "45") (pinfunction "45_45") (pintype "passive"))
    )
    (net (code "78") (name "unconnected-(J12-Pad46)") (class "Default")
      (node (ref "J12") (pin "46") (pinfunction "46_46") (pintype "passive"))
    )
    (net (code "79") (name "unconnected-(J12-Pad47)") (class "Default")
      (node (ref "J12") (pin "47") (pinfunction "47_47") (pintype "passive"))
    )
    (net (code "80") (name "unconnected-(J12-Pad48)") (class "Default")
      (node (ref "J12") (pin "48") (pinfunction "48_48") (pintype "passive"))
    )
    (net (code "81") (name "unconnected-(J12-Pad49)") (class "Default")
      (node (ref "J12") (pin "49") (pinfunction "49_49") (pintype "passive"))
    )
    (net (code "82") (name "unconnected-(J12-Pad50)") (class "Default")
      (node (ref "J12") (pin "50") (pinfunction "50_50") (pintype "passive"))
    )
    (net (code "83") (name "unconnected-(J12-Pad51)") (class "Default")
      (node (ref "J12") (pin "51") (pinfunction "51_51") (pintype "passive"))
    )
    (net (code "84") (name "unconnected-(J13-Pad1)") (class "Default")
      (node (ref "J13") (pin "1") (pinfunction "1_1") (pintype "passive"))
    )
    (net (code "85") (name "unconnected-(J13-Pad2)") (class "Default")
      (node (ref "J13") (pin "2") (pinfunction "2_2") (pintype "passive"))
    )
    (net (code "86") (name "unconnected-(J13-Pad3)") (class "Default")
      (node (ref "J13") (pin "3") (pinfunction "3_3") (pintype "passive"))
    )
    (net (code "87") (name "unconnected-(J14-Pad1)") (class "Default")
      (node (ref "J14") (pin "1") (pinfunction "1_1") (pintype "passive"))
    )
    (net (code "88") (name "unconnected-(J14-Pad2)") (class "Default")
      (node (ref "J14") (pin "2") (pinfunction "2_2") (pintype "passive"))
    )
    (net (code "89") (name "unconnected-(J14-Pad3)") (class "Default")
      (node (ref "J14") (pin "3") (pinfunction "3_3") (pintype "passive"))
    )
    (net (code "90") (name "unconnected-(J14-Pad4)") (class "Default")
      (node (ref "J14") (pin "4") (pinfunction "4_4") (pintype "passive"))
    )
    (net (code "91") (name "unconnected-(J14-Pad5)") (class "Default")
      (node (ref "J14") (pin "5") (pinfunction "5_5") (pintype "passive"))
    )
    (net (code "92") (name "unconnected-(J14-Pad6)") (class "Default")
      (node (ref "J14") (pin "6") (pinfunction "6_6") (pintype "passive"))
    )
    (net (code "93") (name "unconnected-(J14-Pad7)") (class "Default")
      (node (ref "J14") (pin "7") (pinfunction "7_7") (pintype "passive"))
    )
    (net (code "94") (name "unconnected-(J14-Pad8)") (class "Default")
      (node (ref "J14") (pin "8") (pinfunction "8_8") (pintype "passive"))
    )
    (net (code "95") (name "unconnected-(J14-Pad9)") (class "Default")
      (node (ref "J14") (pin "9") (pinfunction "9_9") (pintype "passive"))
    )
    (net (code "96") (name "unconnected-(J14-Pad10)") (class "Default")
      (node (ref "J14") (pin "10") (pinfunction "10_10") (pintype "passive"))
    )
    (net (code "97") (name "unconnected-(J14-Pad11)") (class "Default")
      (node (ref "J14") (pin "11") (pinfunction "11_11") (pintype "passive"))
    )
    (net (code "98") (name "unconnected-(J14-Pad12)") (class "Default")
      (node (ref "J14") (pin "12") (pinfunction "12_12") (pintype "passive"))
    )
    (net (code "99") (name "unconnected-(J14-Pad13)") (class "Default")
      (node (ref "J14") (pin "13") (pinfunction "13_13") (pintype "passive"))
    )
    (net (code "100") (name "unconnected-(J14-Pad14)") (class "Default")
      (node (ref "J14") (pin "14") (pinfunction "14_14") (pintype "passive"))
    )
    (net (code "101") (name "unconnected-(J14-Pad15)") (class "Default")
      (node (ref "J14") (pin "15") (pinfunction "15_15") (pintype "passive"))
    )
    (net (code "102") (name "unconnected-(J14-Pad16)") (class "Default")
      (node (ref "J14") (pin "16") (pinfunction "16_16") (pintype "passive"))
    )
    (net (code "103") (name "unconnected-(J14-Pad17)") (class "Default")
      (node (ref "J14") (pin "17") (pinfunction "17_17") (pintype "passive"))
    )
    (net (code "104") (name "unconnected-(J14-Pad18)") (class "Default")
      (node (ref "J14") (pin "18") (pinfunction "18_18") (pintype "passive"))
    )
    (net (code "105") (name "unconnected-(J14-Pad19)") (class "Default")
      (node (ref "J14") (pin "19") (pinfunction "19_19") (pintype "passive"))
    )
    (net (code "106") (name "unconnected-(J14-Pad20)") (class "Default")
      (node (ref "J14") (pin "20") (pinfunction "20_20") (pintype "passive"))
    )
    (net (code "107") (name "unconnected-(J14-Pad21)") (class "Default")
      (node (ref "J14") (pin "21") (pinfunction "21_21") (pintype "passive"))
    )
    (net (code "108") (name "unconnected-(J14-Pad22)") (class "Default")
      (node (ref "J14") (pin "22") (pinfunction "22_22") (pintype "passive"))
    )
    (net (code "109") (name "unconnected-(J14-Pad23)") (class "Default")
      (node (ref "J14") (pin "23") (pinfunction "23_23") (pintype "passive"))
    )
    (net (code "110") (name "unconnected-(J14-Pad24)") (class "Default")
      (node (ref "J14") (pin "24") (pinfunction "24_24") (pintype "passive"))
    )
    (net (code "111") (name "unconnected-(J14-Pad25)") (class "Default")
      (node (ref "J14") (pin "25") (pinfunction "25_25") (pintype "passive"))
    )
    (net (code "112") (name "unconnected-(J14-Pad26)") (class "Default")
      (node (ref "J14") (pin "26") (pinfunction "26_26") (pintype "passive"))
    )
    (net (code "113") (name "unconnected-(J14-Pad27)") (class "Default")
      (node (ref "J14") (pin "27") (pinfunction "27_27") (pintype "passive"))
    )
    (net (code "114") (name "unconnected-(J14-Pad28)") (class "Default")
      (node (ref "J14") (pin "28") (pinfunction "28_28") (pintype "passive"))
    )
    (net (code "115") (name "unconnected-(J14-Pad29)") (class "Default")
      (node (ref "J14") (pin "29") (pinfunction "29_29") (pintype "passive"))
    )
    (net (code "116") (name "unconnected-(J14-Pad30)") (class "Default")
      (node (ref "J14") (pin "30") (pinfunction "30_30") (pintype "passive"))
    )
    (net (code "117") (name "unconnected-(J14-Pad31)") (class "Default")
      (node (ref "J14") (pin "31") (pinfunction "31_31") (pintype "passive"))
    )
    (net (code "118") (name "unconnected-(J14-Pad32)") (class "Default")
      (node (ref "J14") (pin "32") (pinfunction "32_32") (pintype "passive"))
    )
    (net (code "119") (name "unconnected-(J14-Pad33)") (class "Default")
      (node (ref "J14") (pin "33") (pinfunction "33_33") (pintype "passive"))
    )
    (net (code "120") (name "unconnected-(J14-Pad34)") (class "Default")
      (node (ref "J14") (pin "34") (pinfunction "34_34") (pintype "passive"))
    )
    (net (code "121") (name "unconnected-(J14-Pad35)") (class "Default")
      (node (ref "J14") (pin "35") (pinfunction "35_35") (pintype "passive"))
    )
    (net (code "122") (name "unconnected-(J14-Pad36)") (class "Default")
      (node (ref "J14") (pin "36") (pinfunction "36_36") (pintype "passive"))
    )
    (net (code "123") (name "unconnected-(J14-Pad37)") (class "Default")
      (node (ref "J14") (pin "37") (pinfunction "37_37") (pintype "passive"))
    )
    (net (code "124") (name "unconnected-(J14-Pad38)") (class "Default")
      (node (ref "J14") (pin "38") (pinfunction "38_38") (pintype "passive"))
    )
    (net (code "125") (name "unconnected-(J14-Pad39)") (class "Default")
      (node (ref "J14") (pin "39") (pinfunction "39_39") (pintype "passive"))
    )
    (net (code "126") (name "unconnected-(J14-Pad40)") (class "Default")
      (node (ref "J14") (pin "40") (pinfunction "40_40") (pintype "passive"))
    )
    (net (code "127") (name "unconnected-(J14-Pad41)") (class "Default")
      (node (ref "J14") (pin "41") (pinfunction "41_41") (pintype "passive"))
    )
    (net (code "128") (name "unconnected-(J14-Pad42)") (class "Default")
      (node (ref "J14") (pin "42") (pinfunction "42_42") (pintype "passive"))
    )
    (net (code "129") (name "unconnected-(J14-Pad43)") (class "Default")
      (node (ref "J14") (pin "43") (pinfunction "43_43") (pintype "passive"))
    )
    (net (code "130") (name "unconnected-(J14-Pad44)") (class "Default")
      (node (ref "J14") (pin "44") (pinfunction "44_44") (pintype "passive"))
    )
    (net (code "131") (name "unconnected-(J14-Pad45)") (class "Default")
      (node (ref "J14") (pin "45") (pinfunction "45_45") (pintype "passive"))
    )
    (net (code "132") (name "unconnected-(J14-Pad46)") (class "Default")
      (node (ref "J14") (pin "46") (pinfunction "46_46") (pintype "passive"))
    )
    (net (code "133") (name "unconnected-(J14-Pad47)") (class "Default")
      (node (ref "J14") (pin "47") (pinfunction "47_47") (pintype "passive"))
    )
    (net (code "134") (name "unconnected-(J14-Pad48)") (class "Default")
      (node (ref "J14") (pin "48") (pinfunction "48_48") (pintype "passive"))
    )
    (net (code "135") (name "unconnected-(J14-Pad49)") (class "Default")
      (node (ref "J14") (pin "49") (pinfunction "49_49") (pintype "passive"))
    )
    (net (code "136") (name "unconnected-(J14-Pad50)") (class "Default")
      (node (ref "J14") (pin "50") (pinfunction "50_50") (pintype "passive"))
    )
    (net (code "137") (name "unconnected-(J14-Pad51)") (class "Default")
      (node (ref "J14") (pin "51") (pinfunction "51_51") (pintype "passive"))
    )
    (net (code "138") (name "unconnected-(J18-Pad1)") (class "Default")
      (node (ref "J18") (pin "1") (pinfunction "1_1") (pintype "passive"))
    )
    (net (code "139") (name "unconnected-(J18-Pad2)") (class "Default")
      (node (ref "J18") (pin "2") (pinfunction "2_2") (pintype "passive"))
    )
    (net (code "140") (name "unconnected-(J18-Pad3)") (class "Default")
      (node (ref "J18") (pin "3") (pinfunction "3_3") (pintype "passive"))
    )
    (net (code "141") (name "unconnected-(J19-Pad1)") (class "Default")
      (node (ref "J19") (pin "1") (pinfunction "1_1") (pintype "passive"))
    )
    (net (code "142") (name "unconnected-(J19-Pad2)") (class "Default")
      (node (ref "J19") (pin "2") (pinfunction "2_2") (pintype "passive"))
    )
    (net (code "143") (name "unconnected-(J19-Pad3)") (class "Default")
      (node (ref "J19") (pin "3") (pinfunction "3_3") (pintype "passive"))
    )
    (net (code "144") (name "unconnected-(J19-Pad4)") (class "Default")
      (node (ref "J19") (pin "4") (pinfunction "4_4") (pintype "passive"))
    )
    (net (code "145") (name "unconnected-(J19-Pad5)") (class "Default")
      (node (ref "J19") (pin "5") (pinfunction "5_5") (pintype "passive"))
    )
    (net (code "146") (name "unconnected-(J19-Pad6)") (class "Default")
      (node (ref "J19") (pin "6") (pinfunction "6_6") (pintype "passive"))
    )
    (net (code "147") (name "unconnected-(J19-Pad7)") (class "Default")
      (node (ref "J19") (pin "7") (pinfunction "7_7") (pintype "passive"))
    )
    (net (code "148") (name "unconnected-(J19-Pad8)") (class "Default")
      (node (ref "J19") (pin "8") (pinfunction "8_8") (pintype "passive"))
    )
    (net (code "149") (name "unconnected-(J19-Pad9)") (class "Default")
      (node (ref "J19") (pin "9") (pinfunction "9_9") (pintype "passive"))
    )
    (net (code "150") (name "unconnected-(J19-Pad10)") (class "Default")
      (node (ref "J19") (pin "10") (pinfunction "10_10") (pintype "passive"))
    )
    (net (code "151") (name "unconnected-(J19-Pad11)") (class "Default")
      (node (ref "J19") (pin "11") (pinfunction "11_11") (pintype "passive"))
    )
    (net (code "152") (name "unconnected-(J19-Pad12)") (class "Default")
      (node (ref "J19") (pin "12") (pinfunction "12_12") (pintype "passive"))
    )
    (net (code "153") (name "unconnected-(J19-Pad13)") (class "Default")
      (node (ref "J19") (pin "13") (pinfunction "13_13") (pintype "passive"))
    )
    (net (code "154") (name "unconnected-(J19-Pad14)") (class "Default")
      (node (ref "J19") (pin "14") (pinfunction "14_14") (pintype "passive"))
    )
    (net (code "155") (name "unconnected-(J19-Pad15)") (class "Default")
      (node (ref "J19") (pin "15") (pinfunction "15_15") (pintype "passive"))
    )
    (net (code "156") (name "unconnected-(J19-Pad16)") (class "Default")
      (node (ref "J19") (pin "16") (pinfunction "16_16") (pintype "passive"))
    )
    (net (code "157") (name "unconnected-(J19-Pad17)") (class "Default")
      (node (ref "J19") (pin "17") (pinfunction "17_17") (pintype "passive"))
    )
    (net (code "158") (name "unconnected-(J19-Pad18)") (class "Default")
      (node (ref "J19") (pin "18") (pinfunction "18_18") (pintype "passive"))
    )
    (net (code "159") (name "unconnected-(J19-Pad19)") (class "Default")
      (node (ref "J19") (pin "19") (pinfunction "19_19") (pintype "passive"))
    )
    (net (code "160") (name "unconnected-(J19-Pad20)") (class "Default")
      (node (ref "J19") (pin "20") (pinfunction "20_20") (pintype "passive"))
    )
    (net (code "161") (name "unconnected-(J19-Pad21)") (class "Default")
      (node (ref "J19") (pin "21") (pinfunction "21_21") (pintype "passive"))
    )
    (net (code "162") (name "unconnected-(J19-Pad22)") (class "Default")
      (node (ref "J19") (pin "22") (pinfunction "22_22") (pintype "passive"))
    )
    (net (code "163") (name "unconnected-(J19-Pad23)") (class "Default")
      (node (ref "J19") (pin "23") (pinfunction "23_23") (pintype "passive"))
    )
    (net (code "164") (name "unconnected-(J19-Pad24)") (class "Default")
      (node (ref "J19") (pin "24") (pinfunction "24_24") (pintype "passive"))
    )
    (net (code "165") (name "unconnected-(J19-Pad25)") (class "Default")
      (node (ref "J19") (pin "25") (pinfunction "25_25") (pintype "passive"))
    )
    (net (code "166") (name "unconnected-(J19-Pad26)") (class "Default")
      (node (ref "J19") (pin "26") (pinfunction "26_26") (pintype "passive"))
    )
    (net (code "167") (name "unconnected-(J19-Pad27)") (class "Default")
      (node (ref "J19") (pin "27") (pinfunction "27_27") (pintype "passive"))
    )
    (net (code "168") (name "unconnected-(J19-Pad28)") (class "Default")
      (node (ref "J19") (pin "28") (pinfunction "28_28") (pintype "passive"))
    )
    (net (code "169") (name "unconnected-(J19-Pad29)") (class "Default")
      (node (ref "J19") (pin "29") (pinfunction "29_29") (pintype "passive"))
    )
    (net (code "170") (name "unconnected-(J19-Pad30)") (class "Default")
      (node (ref "J19") (pin "30") (pinfunction "30_30") (pintype "passive"))
    )
    (net (code "171") (name "unconnected-(J19-Pad31)") (class "Default")
      (node (ref "J19") (pin "31") (pinfunction "31_31") (pintype "passive"))
    )
    (net (code "172") (name "unconnected-(J19-Pad32)") (class "Default")
      (node (ref "J19") (pin "32") (pinfunction "32_32") (pintype "passive"))
    )
    (net (code "173") (name "unconnected-(J19-Pad33)") (class "Default")
      (node (ref "J19") (pin "33") (pinfunction "33_33") (pintype "passive"))
    )
    (net (code "174") (name "unconnected-(J19-Pad34)") (class "Default")
      (node (ref "J19") (pin "34") (pinfunction "34_34") (pintype "passive"))
    )
    (net (code "175") (name "unconnected-(J19-Pad35)") (class "Default")
      (node (ref "J19") (pin "35") (pinfunction "35_35") (pintype "passive"))
    )
    (net (code "176") (name "unconnected-(J19-Pad36)") (class "Default")
      (node (ref "J19") (pin "36") (pinfunction "36_36") (pintype "passive"))
    )
    (net (code "177") (name "unconnected-(J19-Pad37)") (class "Default")
      (node (ref "J19") (pin "37") (pinfunction "37_37") (pintype "passive"))
    )
    (net (code "178") (name "unconnected-(J19-Pad38)") (class "Default")
      (node (ref "J19") (pin "38") (pinfunction "38_38") (pintype "passive"))
    )
    (net (code "179") (name "unconnected-(J19-Pad39)") (class "Default")
      (node (ref "J19") (pin "39") (pinfunction "39_39") (pintype "passive"))
    )
    (net (code "180") (name "unconnected-(J19-Pad40)") (class "Default")
      (node (ref "J19") (pin "40") (pinfunction "40_40") (pintype "passive"))
    )
    (net (code "181") (name "unconnected-(J19-Pad41)") (class "Default")
      (node (ref "J19") (pin "41") (pinfunction "41_41") (pintype "passive"))
    )
    (net (code "182") (name "unconnected-(J19-Pad42)") (class "Default")
      (node (ref "J19") (pin "42") (pinfunction "42_42") (pintype "passive"))
    )
    (net (code "183") (name "unconnected-(J19-Pad43)") (class "Default")
      (node (ref "J19") (pin "43") (pinfunction "43_43") (pintype "passive"))
    )
    (net (code "184") (name "unconnected-(J19-Pad44)") (class "Default")
      (node (ref "J19") (pin "44") (pinfunction "44_44") (pintype "passive"))
    )
    (net (code "185") (name "unconnected-(J19-Pad45)") (class "Default")
      (node (ref "J19") (pin "45") (pinfunction "45_45") (pintype "passive"))
    )
    (net (code "186") (name "unconnected-(J19-Pad46)") (class "Default")
      (node (ref "J19") (pin "46") (pinfunction "46_46") (pintype "passive"))
    )
    (net (code "187") (name "unconnected-(J19-Pad47)") (class "Default")
      (node (ref "J19") (pin "47") (pinfunction "47_47") (pintype "passive"))
    )
    (net (code "188") (name "unconnected-(J19-Pad48)") (class "Default")
      (node (ref "J19") (pin "48") (pinfunction "48_48") (pintype "passive"))
    )
    (net (code "189") (name "unconnected-(J19-Pad49)") (class "Default")
      (node (ref "J19") (pin "49") (pinfunction "49_49") (pintype "passive"))
    )
    (net (code "190") (name "unconnected-(J19-Pad50)") (class "Default")
      (node (ref "J19") (pin "50") (pinfunction "50_50") (pintype "passive"))
    )
    (net (code "191") (name "unconnected-(J19-Pad51)") (class "Default")
      (node (ref "J19") (pin "51") (pinfunction "51_51") (pintype "passive"))
    )
    (net (code "192") (name "unconnected-(J20-Pad1)") (class "Default")
      (node (ref "J20") (pin "1") (pinfunction "1_1") (pintype "passive"))
    )
    (net (code "193") (name "unconnected-(J20-Pad2)") (class "Default")
      (node (ref "J20") (pin "2") (pinfunction "2_2") (pintype "passive"))
    )
    (net (code "194") (name "unconnected-(J20-Pad3)") (class "Default")
      (node (ref "J20") (pin "3") (pinfunction "3_3") (pintype "passive"))
    )
    (net (code "195") (name "unconnected-(J23-Pad1)") (class "Default")
      (node (ref "J23") (pin "1") (pinfunction "1_1") (pintype "passive"))
    )
    (net (code "196") (name "unconnected-(J23-Pad2)") (class "Default")
      (node (ref "J23") (pin "2") (pinfunction "2_2") (pintype "passive"))
    )
    (net (code "197") (name "unconnected-(J23-Pad3)") (class "Default")
      (node (ref "J23") (pin "3") (pinfunction "3_3") (pintype "passive"))
    )
    (net (code "198") (name "unconnected-(J23-Pad4)") (class "Default")
      (node (ref "J23") (pin "4") (pinfunction "4_4") (pintype "passive"))
    )
    (net (code "199") (name "unconnected-(J23-Pad5)") (class "Default")
      (node (ref "J23") (pin "5") (pinfunction "5_5") (pintype "passive"))
    )
    (net (code "200") (name "unconnected-(J23-Pad6)") (class "Default")
      (node (ref "J23") (pin "6") (pinfunction "6_6") (pintype "passive"))
    )
    (net (code "201") (name "unconnected-(J23-Pad7)") (class "Default")
      (node (ref "J23") (pin "7") (pinfunction "7_7") (pintype "passive"))
    )
    (net (code "202") (name "unconnected-(J23-Pad8)") (class "Default")
      (node (ref "J23") (pin "8") (pinfunction "8_8") (pintype "passive"))
    )
    (net (code "203") (name "unconnected-(J23-Pad9)") (class "Default")
      (node (ref "J23") (pin "9") (pinfunction "9_9") (pintype "passive"))
    )
    (net (code "204") (name "unconnected-(J23-Pad10)") (class "Default")
      (node (ref "J23") (pin "10") (pinfunction "10_10") (pintype "passive"))
    )
    (net (code "205") (name "unconnected-(J23-Pad11)") (class "Default")
      (node (ref "J23") (pin "11") (pinfunction "11_11") (pintype "passive"))
    )
    (net (code "206") (name "unconnected-(J23-Pad12)") (class "Default")
      (node (ref "J23") (pin "12") (pinfunction "12_12") (pintype "passive"))
    )
    (net (code "207") (name "unconnected-(J23-Pad13)") (class "Default")
      (node (ref "J23") (pin "13") (pinfunction "13_13") (pintype "passive"))
    )
    (net (code "208") (name "unconnected-(J23-Pad14)") (class "Default")
      (node (ref "J23") (pin "14") (pinfunction "14_14") (pintype "passive"))
    )
    (net (code "209") (name "unconnected-(J23-Pad15)") (class "Default")
      (node (ref "J23") (pin "15") (pinfunction "15_15") (pintype "passive"))
    )
    (net (code "210") (name "unconnected-(J23-Pad16)") (class "Default")
      (node (ref "J23") (pin "16") (pinfunction "16_16") (pintype "passive"))
    )
    (net (code "211") (name "unconnected-(J23-Pad17)") (class "Default")
      (node (ref "J23") (pin "17") (pinfunction "17_17") (pintype "passive"))
    )
    (net (code "212") (name "unconnected-(J23-Pad18)") (class "Default")
      (node (ref "J23") (pin "18") (pinfunction "18_18") (pintype "passive"))
    )
    (net (code "213") (name "unconnected-(J23-Pad19)") (class "Default")
      (node (ref "J23") (pin "19") (pinfunction "19_19") (pintype "passive"))
    )
    (net (code "214") (name "unconnected-(J23-Pad20)") (class "Default")
      (node (ref "J23") (pin "20") (pinfunction "20_20") (pintype "passive"))
    )
    (net (code "215") (name "unconnected-(J23-Pad21)") (class "Default")
      (node (ref "J23") (pin "21") (pinfunction "21_21") (pintype "passive"))
    )
    (net (code "216") (name "unconnected-(J23-Pad22)") (class "Default")
      (node (ref "J23") (pin "22") (pinfunction "22_22") (pintype "passive"))
    )
    (net (code "217") (name "unconnected-(J23-Pad23)") (class "Default")
      (node (ref "J23") (pin "23") (pinfunction "23_23") (pintype "passive"))
    )
    (net (code "218") (name "unconnected-(J23-Pad24)") (class "Default")
      (node (ref "J23") (pin "24") (pinfunction "24_24") (pintype "passive"))
    )
    (net (code "219") (name "unconnected-(J23-Pad25)") (class "Default")
      (node (ref "J23") (pin "25") (pinfunction "25_25") (pintype "passive"))
    )
    (net (code "220") (name "unconnected-(J23-Pad26)") (class "Default")
      (node (ref "J23") (pin "26") (pinfunction "26_26") (pintype "passive"))
    )
    (net (code "221") (name "unconnected-(J23-Pad27)") (class "Default")
      (node (ref "J23") (pin "27") (pinfunction "27_27") (pintype "passive"))
    )
    (net (code "222") (name "unconnected-(J23-Pad28)") (class "Default")
      (node (ref "J23") (pin "28") (pinfunction "28_28") (pintype "passive"))
    )
    (net (code "223") (name "unconnected-(J23-Pad29)") (class "Default")
      (node (ref "J23") (pin "29") (pinfunction "29_29") (pintype "passive"))
    )
    (net (code "224") (name "unconnected-(J23-Pad30)") (class "Default")
      (node (ref "J23") (pin "30") (pinfunction "30_30") (pintype "passive"))
    )
    (net (code "225") (name "unconnected-(J23-Pad31)") (class "Default")
      (node (ref "J23") (pin "31") (pinfunction "31_31") (pintype "passive"))
    )
    (net (code "226") (name "unconnected-(J23-Pad32)") (class "Default")
      (node (ref "J23") (pin "32") (pinfunction "32_32") (pintype "passive"))
    )
    (net (code "227") (name "unconnected-(J23-Pad33)") (class "Default")
      (node (ref "J23") (pin "33") (pinfunction "33_33") (pintype "passive"))
    )
    (net (code "228") (name "unconnected-(J23-Pad34)") (class "Default")
      (node (ref "J23") (pin "34") (pinfunction "34_34") (pintype "passive"))
    )
    (net (code "229") (name "unconnected-(J23-Pad35)") (class "Default")
      (node (ref "J23") (pin "35") (pinfunction "35_35") (pintype "passive"))
    )
    (net (code "230") (name "unconnected-(J23-Pad36)") (class "Default")
      (node (ref "J23") (pin "36") (pinfunction "36_36") (pintype "passive"))
    )
    (net (code "231") (name "unconnected-(J23-Pad37)") (class "Default")
      (node (ref "J23") (pin "37") (pinfunction "37_37") (pintype "passive"))
    )
    (net (code "232") (name "unconnected-(J23-Pad38)") (class "Default")
      (node (ref "J23") (pin "38") (pinfunction "38_38") (pintype "passive"))
    )
    (net (code "233") (name "unconnected-(J23-Pad39)") (class "Default")
      (node (ref "J23") (pin "39") (pinfunction "39_39") (pintype "passive"))
    )
    (net (code "234") (name "unconnected-(J23-Pad40)") (class "Default")
      (node (ref "J23") (pin "40") (pinfunction "40_40") (pintype "passive"))
    )
    (net (code "235") (name "unconnected-(J23-Pad41)") (class "Default")
      (node (ref "J23") (pin "41") (pinfunction "41_41") (pintype "passive"))
    )
    (net (code "236") (name "unconnected-(J23-Pad42)") (class "Default")
      (node (ref "J23") (pin "42") (pinfunction "42_42") (pintype "passive"))
    )
    (net (code "237") (name "unconnected-(J23-Pad43)") (class "Default")
      (node (ref "J23") (pin "43") (pinfunction "43_43") (pintype "passive"))
    )
    (net (code "238") (name "unconnected-(J23-Pad44)") (class "Default")
      (node (ref "J23") (pin "44") (pinfunction "44_44") (pintype "passive"))
    )
    (net (code "239") (name "unconnected-(J23-Pad45)") (class "Default")
      (node (ref "J23") (pin "45") (pinfunction "45_45") (pintype "passive"))
    )
    (net (code "240") (name "unconnected-(J23-Pad46)") (class "Default")
      (node (ref "J23") (pin "46") (pinfunction "46_46") (pintype "passive"))
    )
    (net (code "241") (name "unconnected-(J23-Pad47)") (class "Default")
      (node (ref "J23") (pin "47") (pinfunction "47_47") (pintype "passive"))
    )
    (net (code "242") (name "unconnected-(J23-Pad48)") (class "Default")
      (node (ref "J23") (pin "48") (pinfunction "48_48") (pintype "passive"))
    )
    (net (code "243") (name "unconnected-(J23-Pad49)") (class "Default")
      (node (ref "J23") (pin "49") (pinfunction "49_49") (pintype "passive"))
    )
    (net (code "244") (name "unconnected-(J23-Pad50)") (class "Default")
      (node (ref "J23") (pin "50") (pinfunction "50_50") (pintype "passive"))
    )
    (net (code "245") (name "unconnected-(J23-Pad51)") (class "Default")
      (node (ref "J23") (pin "51") (pinfunction "51_51") (pintype "passive"))
    )
  )
)
